# QSTL_M12C_BNC.net
KiCad netlist of a schematic drawn in Altium Designer
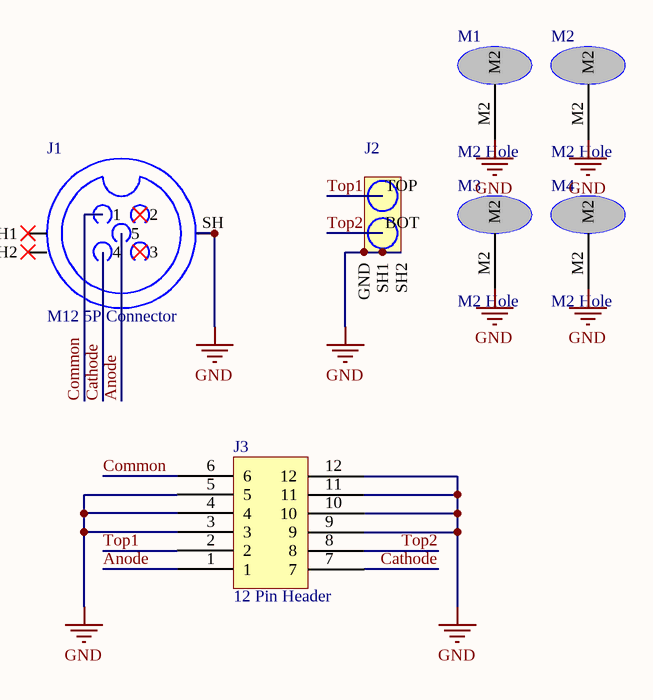
[diagram p0: QSTL_M12C_BNC.SchDoc]

(export (version "E")
  (design (tool "Eeschema 10.0.6"))
  (components
    (comp (ref "J1")
      (value "M12 5P Connector")
      (footprint "861-B05-213R004")
      (libsource (lib "QSTL_M12C_BNC") (part "861-B05-213R004"))
    )
    (comp (ref "J2")
      (value "Stacked BNC")
      (footprint "031-6590")
      (description "https://www.digikey.ca/en/products/detail/amphenol-rf/031-6590/4037245")
      (libsource (lib "QSTL_M12C_BNC") (part "031-6590"))
    )
    (comp (ref "J3")
      (value "12 Pin Header")
      (footprint "PZ254-2-06-S")
      (description "https://jlcpcb.com/partdetail/HCTL-PZ254_2_06S/C3294464")
      (libsource (lib "QSTL_M12C_BNC") (part "PZ254-2-06-S"))
    )
    (comp (ref "M1")
      (value "M2 Hole")
      (footprint "M2_Hole")
      (libsource (lib "QSTL_M12C_BNC") (part "M2_Hole"))
    )
    (comp (ref "M2")
      (value "M2 Hole")
      (footprint "M2_Hole")
      (libsource (lib "QSTL_M12C_BNC") (part "M2_Hole"))
    )
    (comp (ref "M3")
      (value "M2 Hole")
      (footprint "M2_Hole")
      (libsource (lib "QSTL_M12C_BNC") (part "M2_Hole"))
    )
    (comp (ref "M4")
      (value "M2 Hole")
      (footprint "M2_Hole")
      (libsource (lib "QSTL_M12C_BNC") (part "M2_Hole"))
    )
  )
  (nets
    (net (code "1") (name "/Anode") (class "Default")
      (node (ref "J1") (pin "5") (pinfunction "5_5") (pintype "passive"))
      (node (ref "J3") (pin "1") (pinfunction "1_1") (pintype "passive"))
    )
    (net (code "2") (name "/Cathode") (class "Default")
      (node (ref "J1") (pin "4") (pinfunction "4_4") (pintype "passive"))
      (node (ref "J3") (pin "7") (pinfunction "7_7") (pintype "passive"))
    )
    (net (code "3") (name "/Common") (class "Default")
      (node (ref "J1") (pin "1") (pinfunction "1_1") (pintype "passive"))
      (node (ref "J3") (pin "6") (pinfunction "6_6") (pintype "passive"))
    )
    (net (code "4") (name "/Top1") (class "Default")
      (node (ref "J2") (pin "TOP") (pinfunction "TOP_TOP") (pintype "passive"))
      (node (ref "J3") (pin "2") (pinfunction "2_2") (pintype "passive"))
    )
    (net (code "5") (name "/Top2") (class "Default")
      (node (ref "J2") (pin "BOT") (pinfunction "BOT_BOT") (pintype "passive"))
      (node (ref "J3") (pin "8") (pinfunction "8_8") (pintype "passive"))
    )
    (net (code "6") (name "GND") (class "Default")
      (node (ref "J1") (pin "SH") (pinfunction "SH_SH") (pintype "passive"))
      (node (ref "J2") (pin "GND") (pinfunction "GND_GND") (pintype "passive"))
      (node (ref "J2") (pin "SH1") (pinfunction "SH1_SH1") (pintype "passive"))
      (node (ref "J2") (pin "SH2") (pinfunction "SH2_SH2") (pintype "passive"))
      (node (ref "J3") (pin "10") (pinfunction "10_10") (pintype "passive"))
      (node (ref "J3") (pin "11") (pinfunction "11_11") (pintype "passive"))
      (node (ref "J3") (pin "12") (pinfunction "12_12") (pintype "passive"))
      (node (ref "J3") (pin "3") (pinfunction "3_3") (pintype "passive"))
      (node (ref "J3") (pin "4") (pinfunction "4_4") (pintype "passive"))
      (node (ref "J3") (pin "5") (pinfunction "5_5") (pintype "passive"))
      (node (ref "J3") (pin "9") (pinfunction "9_9") (pintype "passive"))
      (node (ref "M1") (pin "M2") (pinfunction "M2_M2") (pintype "passive"))
      (node (ref "M2") (pin "M2") (pinfunction "M2_M2") (pintype "passive"))
      (node (ref "M3") (pin "M2") (pinfunction "M2_M2") (pintype "passive"))
      (node (ref "M4") (pin "M2") (pinfunction "M2_M2") (pintype "passive"))
    )
    (net (code "7") (name "unconnected-(J1-Pad2)") (class "Default")
      (node (ref "J1") (pin "2") (pinfunction "2_2") (pintype "passive+no_connect"))
    )
    (net (code "8") (name "unconnected-(J1-Pad3)") (class "Default")
      (node (ref "J1") (pin "3") (pinfunction "3_3") (pintype "passive+no_connect"))
    )
    (net (code "9") (name "unconnected-(J1-PadMH1)") (class "Default")
      (node (ref "J1") (pin "MH1") (pinfunction "MH1_MH1") (pintype "passive"))
    )
    (net (code "10") (name "unconnected-(J1-PadMH2)") (class "Default")
      (node (ref "J1") (pin "MH2") (pinfunction "MH2_MH2") (pintype "passive"))
    )
  )
)
